# TopLevel.net
KiCad netlist of a schematic drawn in Altium Designer
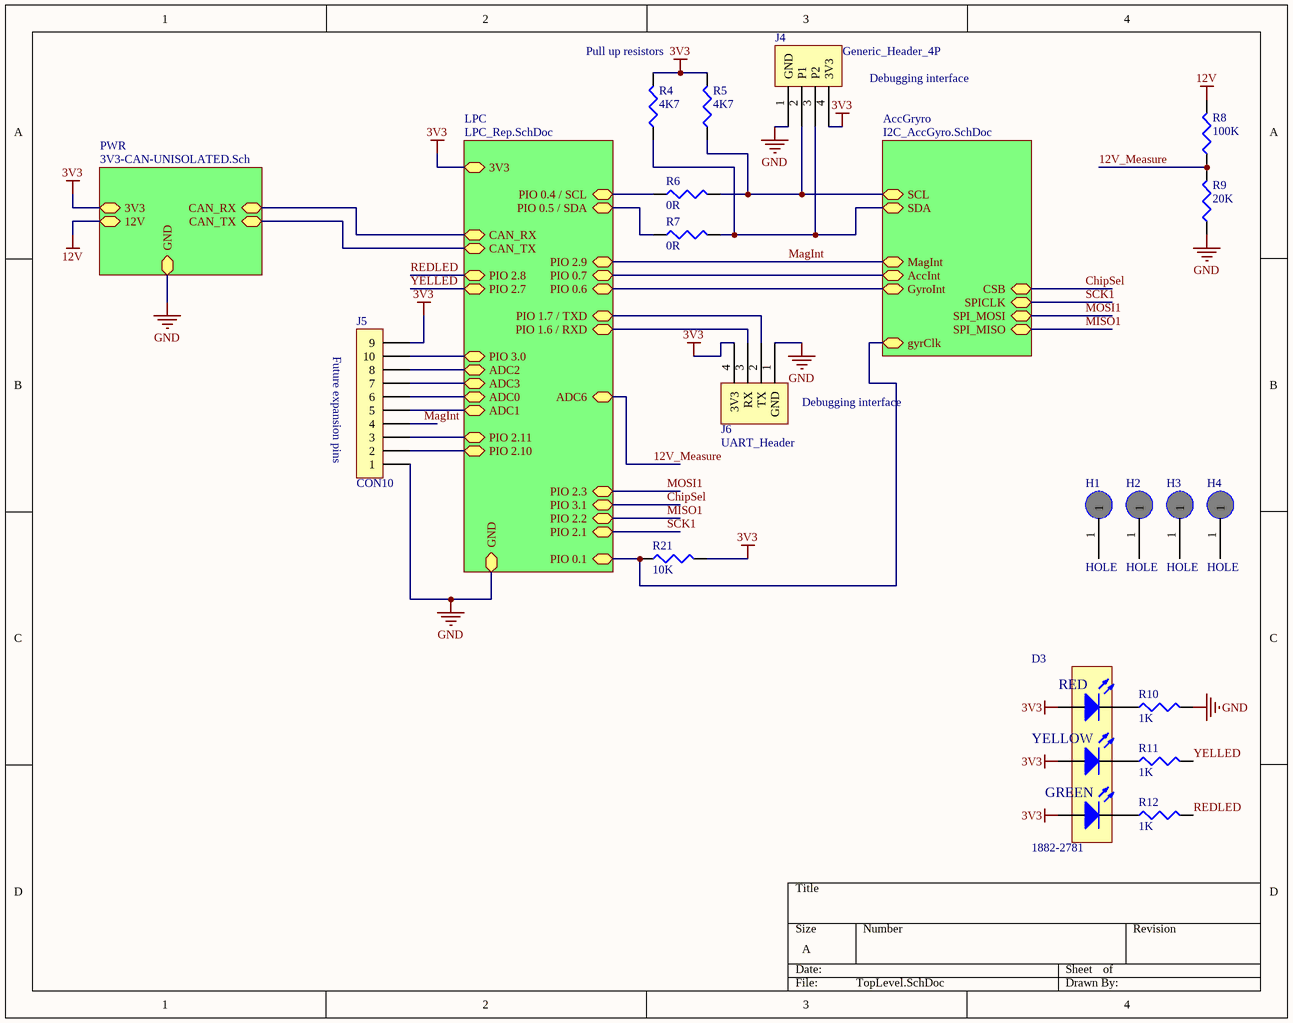
[diagram p0: TopLevel.SchDoc]

(export (version "E")
  (design (tool "Eeschema 10.0.6"))
  (components
    (comp (ref "D3")
      (value "1882-2781")
      (footprint "LED_TRILEVEL")
      (description "Three level LED")
      (libsource (lib "RCLDQ") (part "LED-TRILEVEL"))
    )
    (comp (ref "H1")
      (value "HOLE")
      (footprint "M2.5")
      (description "Hole")
      (libsource (lib "Miscellaneous") (part "HOLE"))
    )
    (comp (ref "H2")
      (value "HOLE")
      (footprint "M2.5")
      (description "Hole")
      (libsource (lib "Miscellaneous") (part "HOLE"))
    )
    (comp (ref "H3")
      (value "HOLE")
      (footprint "M2.5")
      (description "Hole")
      (libsource (lib "Miscellaneous") (part "HOLE"))
    )
    (comp (ref "H4")
      (value "HOLE")
      (footprint "M2.5")
      (description "Hole")
      (libsource (lib "Miscellaneous") (part "HOLE"))
    )
    (comp (ref "J4")
      (value "Generic_Header_4P")
      (footprint "IDC4")
      (libsource (lib "2009_BatteryMaster") (part "Generic_Header_4P"))
    )
    (comp (ref "J5")
      (value "CON10")
      (footprint "IDC10")
      (description "10 pin, right angle, ribbon con with claws")
      (libsource (lib "2009_BatteryMaster") (part "CON10"))
    )
    (comp (ref "J6")
      (value "UART_Header")
      (footprint "IDC4")
      (libsource (lib "2009_BatteryMaster") (part "UART_Header"))
    )
    (comp (ref "R4")
      (value "4K7")
      (footprint "0603")
      (description "Resistor")
      (libsource (lib "RCLDQ") (part "RES1"))
    )
    (comp (ref "R5")
      (value "4K7")
      (footprint "0603")
      (description "Resistor")
      (libsource (lib "RCLDQ") (part "RES1"))
    )
    (comp (ref "R6")
      (value "0R")
      (footprint "0603")
      (description "Resistor")
      (libsource (lib "2009_BatteryMaster") (part "RES1"))
    )
    (comp (ref "R7")
      (value "0R")
      (footprint "0603")
      (description "Resistor")
      (libsource (lib "2009_BatteryMaster") (part "RES1"))
    )
    (comp (ref "R8")
      (value "100K")
      (footprint "0603")
      (description "Resistor")
      (libsource (lib "2009_BatteryMaster") (part "RES1"))
    )
    (comp (ref "R9")
      (value "20K")
      (footprint "0603")
      (description "Resistor")
      (libsource (lib "2009_BatteryMaster") (part "RES1"))
    )
    (comp (ref "R10")
      (value "1K")
      (footprint "0603")
      (description "Resistor")
      (libsource (lib "RCLDQ") (part "RES1"))
    )
    (comp (ref "R11")
      (value "1K")
      (footprint "0603")
      (description "Resistor")
      (libsource (lib "RCLDQ") (part "RES1"))
    )
    (comp (ref "R12")
      (value "1K")
      (footprint "0603")
      (description "Resistor")
      (libsource (lib "RCLDQ") (part "RES1"))
    )
    (comp (ref "R21")
      (value "10K")
      (footprint "0603")
      (description "Resistor")
      (libsource (lib "RCLDQ") (part "RES1"))
    )
  )
  (nets
    (net (code "1") (name "/12V_Measure") (class "Default")
      (node (ref "R8") (pin "1") (pinfunction "1_1") (pintype "passive"))
      (node (ref "R9") (pin "2") (pinfunction "2_2") (pintype "passive"))
    )
    (net (code "2") (name "/ADC0") (class "Default")
      (node (ref "J5") (pin "6") (pinfunction "6_6") (pintype "passive"))
    )
    (net (code "3") (name "/ADC1") (class "Default")
      (node (ref "J5") (pin "5") (pinfunction "5_5") (pintype "passive"))
    )
    (net (code "4") (name "/ADC2") (class "Default")
      (node (ref "J5") (pin "8") (pinfunction "8_8") (pintype "passive"))
    )
    (net (code "5") (name "/ADC3") (class "Default")
      (node (ref "J5") (pin "7") (pinfunction "7_7") (pintype "passive"))
    )
    (net (code "13") (name "/MagInt") (class "Default")
      (node (ref "J5") (pin "4") (pinfunction "4_4") (pintype "passive"))
    )
    (net (code "14") (name "/PIO 0.1") (class "Default")
      (node (ref "R21") (pin "1") (pinfunction "1_1") (pintype "passive"))
    )
    (net (code "15") (name "/PIO 0.4 {slash} SCL") (class "Default")
      (node (ref "R6") (pin "1") (pinfunction "1_1") (pintype "passive"))
    )
    (net (code "16") (name "/PIO 0.5 {slash} SDA") (class "Default")
      (node (ref "R7") (pin "1") (pinfunction "1_1") (pintype "passive"))
    )
    (net (code "17") (name "/PIO 1.6 {slash} RXD") (class "Default")
      (node (ref "J6") (pin "3") (pinfunction "RX_3") (pintype "passive"))
    )
    (net (code "18") (name "/PIO 1.7 {slash} TXD") (class "Default")
      (node (ref "J6") (pin "2") (pinfunction "TX_2") (pintype "passive"))
    )
    (net (code "19") (name "/PIO 2.10") (class "Default")
      (node (ref "J5") (pin "2") (pinfunction "2_2") (pintype "passive"))
    )
    (net (code "20") (name "/PIO 2.11") (class "Default")
      (node (ref "J5") (pin "3") (pinfunction "3_3") (pintype "passive"))
    )
    (net (code "21") (name "/PIO 3.0") (class "Default")
      (node (ref "J5") (pin "10") (pinfunction "10_10") (pintype "passive"))
    )
    (net (code "22") (name "/REDLED") (class "Default")
      (node (ref "R12") (pin "2") (pinfunction "2_2") (pintype "passive"))
    )
    (net (code "24") (name "/SCL") (class "Default")
      (node (ref "J4") (pin "2") (pinfunction "P1_2") (pintype "passive"))
      (node (ref "R5") (pin "1") (pinfunction "1_1") (pintype "passive"))
      (node (ref "R6") (pin "2") (pinfunction "2_2") (pintype "passive"))
    )
    (net (code "25") (name "/SDA") (class "Default")
      (node (ref "J4") (pin "3") (pinfunction "P2_3") (pintype "passive"))
      (node (ref "R4") (pin "1") (pinfunction "1_1") (pintype "passive"))
      (node (ref "R7") (pin "2") (pinfunction "2_2") (pintype "passive"))
    )
    (net (code "26") (name "/YELLED") (class "Default")
      (node (ref "R11") (pin "2") (pinfunction "2_2") (pintype "passive"))
    )
    (net (code "27") (name "3V3") (class "Default")
      (node (ref "D3") (pin "4") (pinfunction "A_4") (pintype "passive"))
      (node (ref "D3") (pin "5") (pinfunction "A_5") (pintype "passive"))
      (node (ref "D3") (pin "6") (pinfunction "A_6") (pintype "passive"))
      (node (ref "J4") (pin "4") (pinfunction "3V3_4") (pintype "passive"))
      (node (ref "J5") (pin "9") (pinfunction "9_9") (pintype "passive"))
      (node (ref "J6") (pin "4") (pinfunction "3V3_4") (pintype "passive"))
      (node (ref "R21") (pin "2") (pinfunction "2_2") (pintype "passive"))
      (node (ref "R4") (pin "2") (pinfunction "2_2") (pintype "passive"))
      (node (ref "R5") (pin "2") (pinfunction "2_2") (pintype "passive"))
    )
    (net (code "28") (name "12V") (class "Default")
      (node (ref "R8") (pin "2") (pinfunction "2_2") (pintype "passive"))
    )
    (net (code "29") (name "GND") (class "Default")
      (node (ref "J4") (pin "1") (pinfunction "GND_1") (pintype "passive"))
      (node (ref "J5") (pin "1") (pinfunction "1_1") (pintype "passive"))
      (node (ref "J6") (pin "1") (pinfunction "GND_1") (pintype "passive"))
      (node (ref "R10") (pin "2") (pinfunction "2_2") (pintype "passive"))
      (node (ref "R9") (pin "1") (pinfunction "1_1") (pintype "passive"))
    )
    (net (code "30") (name "Net-(D3-K-Pad1)") (class "Default")
      (node (ref "D3") (pin "1") (pinfunction "K_1") (pintype "passive"))
      (node (ref "R12") (pin "1") (pinfunction "1_1") (pintype "passive"))
    )
    (net (code "31") (name "Net-(D3-K-Pad2)") (class "Default")
      (node (ref "D3") (pin "2") (pinfunction "K_2") (pintype "passive"))
      (node (ref "R11") (pin "1") (pinfunction "1_1") (pintype "passive"))
    )
    (net (code "32") (name "Net-(D3-K-Pad3)") (class "Default")
      (node (ref "D3") (pin "3") (pinfunction "K_3") (pintype "passive"))
      (node (ref "R10") (pin "1") (pinfunction "1_1") (pintype "passive"))
    )
    (net (code "33") (name "unconnected-(H1-Pad1)") (class "Default")
      (node (ref "H1") (pin "1") (pinfunction "1_1") (pintype "passive"))
    )
    (net (code "34") (name "unconnected-(H2-Pad1)") (class "Default")
      (node (ref "H2") (pin "1") (pinfunction "1_1") (pintype "passive"))
    )
    (net (code "35") (name "unconnected-(H3-Pad1)") (class "Default")
      (node (ref "H3") (pin "1") (pinfunction "1_1") (pintype "passive"))
    )
    (net (code "36") (name "unconnected-(H4-Pad1)") (class "Default")
      (node (ref "H4") (pin "1") (pinfunction "1_1") (pintype "passive"))
    )
  )
)
